# Analog_Electronics_Fundamentals_103_-_La.net
KiCad netlist of a schematic drawn in EAGLE
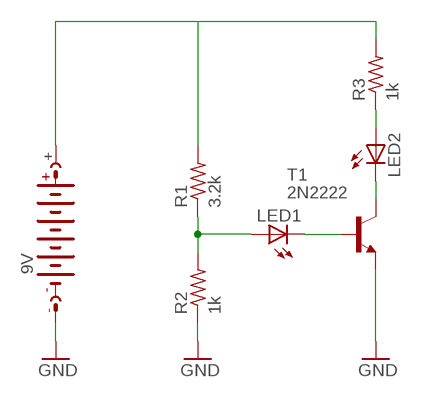
[diagram p0: schematic, sheet 1]

(export (version "E")
  (design (tool "Eeschema 10.0.6"))
  (components
    (comp (ref "9V")
      (value "AB9V")
      (footprint "eagle-import:AB9V")
      (libsource (lib "eagle-import") (part "AB9V"))
    )
    (comp (ref "LED1")
      (value "LED5MM")
      (footprint "eagle-import:LED5MM")
      (libsource (lib "eagle-import") (part "LED5MM"))
    )
    (comp (ref "LED2")
      (value "LED5MM")
      (footprint "eagle-import:LED5MM")
      (libsource (lib "eagle-import") (part "LED5MM"))
    )
    (comp (ref "R1")
      (value "3.2k")
      (footprint "eagle-import:0204_7")
      (libsource (lib "eagle-import") (part "R-US_0204/7"))
    )
    (comp (ref "R2")
      (value "1k")
      (footprint "eagle-import:0204_7")
      (libsource (lib "eagle-import") (part "R-US_0204/7"))
    )
    (comp (ref "R3")
      (value "1k")
      (footprint "eagle-import:0204_7")
      (libsource (lib "eagle-import") (part "R-US_0204/7"))
    )
    (comp (ref "T1")
      (value "2N2222")
      (footprint "eagle-import:TO92-EBC-OVAL")
      (libsource (lib "eagle-import") (part "2N2222"))
    )
  )
  (nets
    (net (code "1") (name "GND") (class "Default")
      (node (ref "9V") (pin "-") (pinfunction "-_-") (pintype "passive"))
      (node (ref "R2") (pin "1") (pinfunction "1_1") (pintype "passive"))
      (node (ref "T1") (pin "E") (pinfunction "E_E") (pintype "passive"))
    )
    (net (code "2") (name "Net-(9V-Pad+)") (class "Default")
      (node (ref "9V") (pin "+") (pinfunction "+_+") (pintype "passive"))
      (node (ref "R1") (pin "2") (pinfunction "2_2") (pintype "passive"))
      (node (ref "R3") (pin "2") (pinfunction "2_2") (pintype "passive"))
    )
    (net (code "3") (name "Net-(LED1-C)") (class "Default")
      (node (ref "LED1") (pin "K") (pinfunction "C_K") (pintype "passive"))
      (node (ref "T1") (pin "B") (pinfunction "B_B") (pintype "passive"))
    )
    (net (code "4") (name "Net-(LED1-PadA)") (class "Default")
      (node (ref "LED1") (pin "A") (pinfunction "A_A") (pintype "passive"))
      (node (ref "R1") (pin "1") (pinfunction "1_1") (pintype "passive"))
      (node (ref "R2") (pin "2") (pinfunction "2_2") (pintype "passive"))
    )
    (net (code "5") (name "Net-(LED2-C)") (class "Default")
      (node (ref "LED2") (pin "K") (pinfunction "C_K") (pintype "passive"))
      (node (ref "T1") (pin "C") (pinfunction "C_C") (pintype "passive"))
    )
    (net (code "6") (name "Net-(LED2-PadA)") (class "Default")
      (node (ref "LED2") (pin "A") (pinfunction "A_A") (pintype "passive"))
      (node (ref "R3") (pin "1") (pinfunction "1_1") (pintype "passive"))
    )
  )
)
